# pqm_v2_page3.net
KiCad netlist of a schematic drawn in Altium Designer
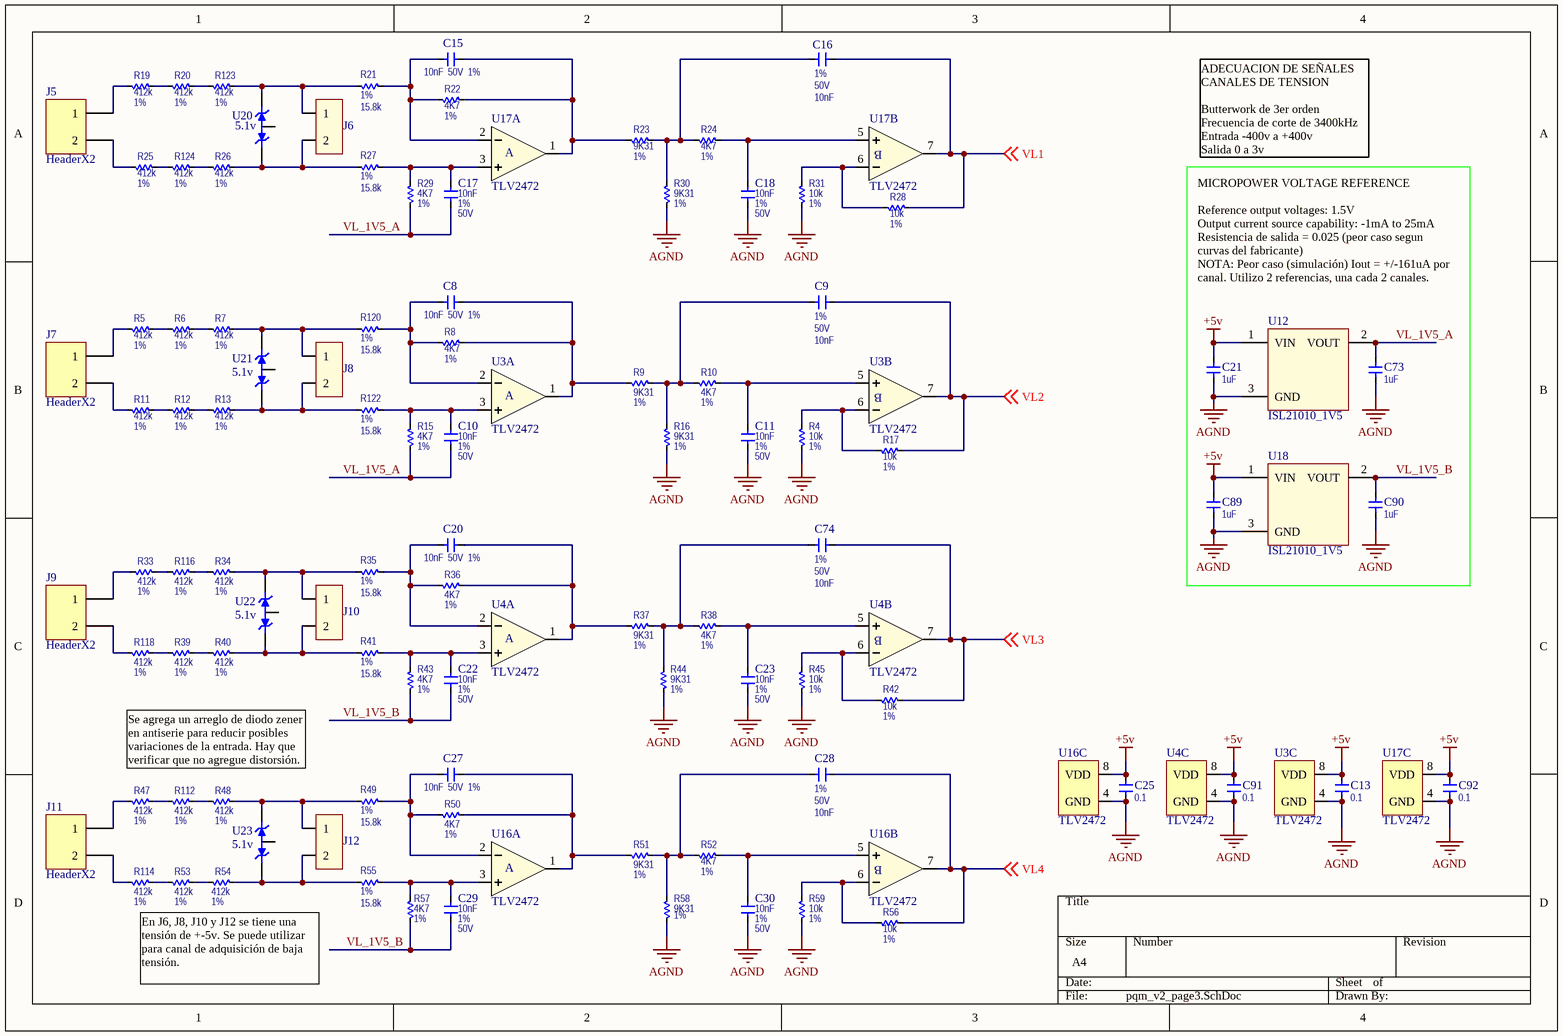
[diagram p0: pqm_v2_page3.SchDoc]

(export (version "E")
  (design (tool "Eeschema 10.0.6"))
  (components
    (comp (ref "C8")
      (value "10nF")
      (footprint "CAPC2013X110N")
      (description "CAP CER 10000PF 50V NP0 0805")
      (fields
        (field (name "MANUFACTURER") "Murata Electronics North America")
        (field (name "TOLERANCE") "1%")
        (field (name "VOLTAGE RATING") "50V")
        (field (name "DIGIKEY PART NUMBER") "490-8295-1-ND")
      )
      (libsource (lib "pqm_v2_lib_cap") (part "CAP_GRM2195C1H103FA01D_MURATA"))
    )
    (comp (ref "C9")
      (value "10nF")
      (footprint "CAPC2013X110N")
      (description "CAP CER 10000PF 50V NP0 0805")
      (fields
        (field (name "MANUFACTURER") "Murata Electronics North America")
        (field (name "TOLERANCE") "1%")
        (field (name "VOLTAGE RATING") "50V")
        (field (name "DIGIKEY PART NUMBER") "490-8295-1-ND")
      )
      (libsource (lib "pqm_v2_lib_cap") (part "CAP_GRM2195C1H103FA01D_MURATA"))
    )
    (comp (ref "C10")
      (value "10nF")
      (footprint "CAPC2013X110N")
      (description "CAP CER 10000PF 50V NP0 0805")
      (fields
        (field (name "MANUFACTURER") "Murata Electronics North America")
        (field (name "TOLERANCE") "1%")
        (field (name "VOLTAGE RATING") "50V")
        (field (name "DIGIKEY PART NUMBER") "490-8295-1-ND")
      )
      (libsource (lib "pqm_v2_lib_cap") (part "CAP_GRM2195C1H103FA01D_MURATA"))
    )
    (comp (ref "C11")
      (value "10nF")
      (footprint "CAPC2013X110N")
      (description "CAP CER 10000PF 50V NP0 0805")
      (fields
        (field (name "MANUFACTURER") "Murata Electronics North America")
        (field (name "TOLERANCE") "1%")
        (field (name "VOLTAGE RATING") "50V")
        (field (name "DIGIKEY PART NUMBER") "490-8295-1-ND")
      )
      (libsource (lib "pqm_v2_lib_cap") (part "CAP_GRM2195C1H103FA01D_MURATA"))
    )
    (comp (ref "C13")
      (value "0.1")
      (footprint "CAPC2013X110N")
      (description "CAP CER 0.1UF 25V 10% X7R 0805")
      (fields (field (name "MANUFACTURER") "Yageo") (field (name "TOLERANCE") "10%"))
      (libsource (lib "pqm_v2_lib_cap") (part "CAP_CC0805KRX7R8BB104_YAGEO"))
    )
    (comp (ref "C15")
      (value "10nF")
      (footprint "CAPC2013X110N")
      (description "CAP CER 10000PF 50V NP0 0805")
      (fields
        (field (name "MANUFACTURER") "Murata Electronics North America")
        (field (name "TOLERANCE") "1%")
        (field (name "VOLTAGE RATING") "50V")
        (field (name "DIGIKEY PART NUMBER") "490-8295-1-ND")
      )
      (libsource (lib "pqm_v2_lib_cap") (part "CAP_GRM2195C1H103FA01D_MURATA"))
    )
    (comp (ref "C16")
      (value "10nF")
      (footprint "CAPC2013X110N")
      (description "CAP CER 10000PF 50V NP0 0805")
      (fields
        (field (name "MANUFACTURER") "Murata Electronics North America")
        (field (name "TOLERANCE") "1%")
        (field (name "VOLTAGE RATING") "50V")
        (field (name "DIGIKEY PART NUMBER") "490-8295-1-ND")
      )
      (libsource (lib "pqm_v2_lib_cap") (part "CAP_GRM2195C1H103FA01D_MURATA"))
    )
    (comp (ref "C17")
      (value "10nF")
      (footprint "CAPC2013X110N")
      (description "CAP CER 10000PF 50V NP0 0805")
      (fields
        (field (name "MANUFACTURER") "Murata Electronics North America")
        (field (name "TOLERANCE") "1%")
        (field (name "VOLTAGE RATING") "50V")
        (field (name "DIGIKEY PART NUMBER") "490-8295-1-ND")
      )
      (libsource (lib "pqm_v2_lib_cap") (part "CAP_GRM2195C1H103FA01D_MURATA"))
    )
    (comp (ref "C18")
      (value "10nF")
      (footprint "CAPC2013X110N")
      (description "CAP CER 10000PF 50V NP0 0805")
      (fields
        (field (name "MANUFACTURER") "Murata Electronics North America")
        (field (name "TOLERANCE") "1%")
        (field (name "VOLTAGE RATING") "50V")
        (field (name "DIGIKEY PART NUMBER") "490-8295-1-ND")
      )
      (libsource (lib "pqm_v2_lib_cap") (part "CAP_GRM2195C1H103FA01D_MURATA"))
    )
    (comp (ref "C20")
      (value "10nF")
      (footprint "CAPC2013X110N")
      (description "CAP CER 10000PF 50V NP0 0805")
      (fields
        (field (name "MANUFACTURER") "Murata Electronics North America")
        (field (name "TOLERANCE") "1%")
        (field (name "VOLTAGE RATING") "50V")
        (field (name "DIGIKEY PART NUMBER") "490-8295-1-ND")
      )
      (libsource (lib "pqm_v2_lib_cap") (part "CAP_GRM2195C1H103FA01D_MURATA"))
    )
    (comp (ref "C21")
      (value "1uF")
      (footprint "CAPC2013X110N")
      (description "CAP CER 1UF 16V X7R 0805")
      (fields (field (name "MANUFACTURER") "YAGEO") (field (name "TOLERANCE") "10%"))
      (libsource (lib "pqm_v2_lib_cap") (part "CAP_CC0805KKX7R7BB105_YAGEO"))
    )
    (comp (ref "C22")
      (value "10nF")
      (footprint "CAPC2013X110N")
      (description "CAP CER 10000PF 50V NP0 0805")
      (fields
        (field (name "MANUFACTURER") "Murata Electronics North America")
        (field (name "TOLERANCE") "1%")
        (field (name "VOLTAGE RATING") "50V")
        (field (name "DIGIKEY PART NUMBER") "490-8295-1-ND")
      )
      (libsource (lib "pqm_v2_lib_cap") (part "CAP_GRM2195C1H103FA01D_MURATA"))
    )
    (comp (ref "C23")
      (value "10nF")
      (footprint "CAPC2013X110N")
      (description "CAP CER 10000PF 50V NP0 0805")
      (fields
        (field (name "MANUFACTURER") "Murata Electronics North America")
        (field (name "TOLERANCE") "1%")
        (field (name "VOLTAGE RATING") "50V")
        (field (name "DIGIKEY PART NUMBER") "490-8295-1-ND")
      )
      (libsource (lib "pqm_v2_lib_cap") (part "CAP_GRM2195C1H103FA01D_MURATA"))
    )
    (comp (ref "C25")
      (value "0.1")
      (footprint "CAPC2013X110N")
      (description "CAP CER 0.1UF 25V 10% X7R 0805")
      (fields (field (name "MANUFACTURER") "Yageo") (field (name "TOLERANCE") "10%"))
      (libsource (lib "pqm_v2_lib_cap") (part "CAP_CC0805KRX7R8BB104_YAGEO"))
    )
    (comp (ref "C27")
      (value "10nF")
      (footprint "CAPC2013X110N")
      (description "CAP CER 10000PF 50V NP0 0805")
      (fields
        (field (name "MANUFACTURER") "Murata Electronics North America")
        (field (name "TOLERANCE") "1%")
        (field (name "VOLTAGE RATING") "50V")
        (field (name "DIGIKEY PART NUMBER") "490-8295-1-ND")
      )
      (libsource (lib "pqm_v2_lib_cap") (part "CAP_GRM2195C1H103FA01D_MURATA"))
    )
    (comp (ref "C28")
      (value "10nF")
      (footprint "CAPC2013X110N")
      (description "CAP CER 10000PF 50V NP0 0805")
      (fields
        (field (name "MANUFACTURER") "Murata Electronics North America")
        (field (name "TOLERANCE") "1%")
        (field (name "VOLTAGE RATING") "50V")
        (field (name "DIGIKEY PART NUMBER") "490-8295-1-ND")
      )
      (libsource (lib "pqm_v2_lib_cap") (part "CAP_GRM2195C1H103FA01D_MURATA"))
    )
    (comp (ref "C29")
      (value "10nF")
      (footprint "CAPC2013X110N")
      (description "CAP CER 10000PF 50V NP0 0805")
      (fields
        (field (name "MANUFACTURER") "Murata Electronics North America")
        (field (name "TOLERANCE") "1%")
        (field (name "VOLTAGE RATING") "50V")
        (field (name "DIGIKEY PART NUMBER") "490-8295-1-ND")
      )
      (libsource (lib "pqm_v2_lib_cap") (part "CAP_GRM2195C1H103FA01D_MURATA"))
    )
    (comp (ref "C30")
      (value "10nF")
      (footprint "CAPC2013X110N")
      (description "CAP CER 10000PF 50V NP0 0805")
      (fields
        (field (name "MANUFACTURER") "Murata Electronics North America")
        (field (name "TOLERANCE") "1%")
        (field (name "VOLTAGE RATING") "50V")
        (field (name "DIGIKEY PART NUMBER") "490-8295-1-ND")
      )
      (libsource (lib "pqm_v2_lib_cap") (part "CAP_GRM2195C1H103FA01D_MURATA"))
    )
    (comp (ref "C73")
      (value "1uF")
      (footprint "CAPC2013X110N")
      (description "CAP CER 1UF 16V X7R 0805")
      (fields (field (name "MANUFACTURER") "YAGEO") (field (name "TOLERANCE") "10%"))
      (libsource (lib "pqm_v2_lib_cap") (part "CAP_CC0805KKX7R7BB105_YAGEO"))
    )
    (comp (ref "C74")
      (value "10nF")
      (footprint "CAPC2013X110N")
      (description "CAP CER 10000PF 50V NP0 0805")
      (fields
        (field (name "MANUFACTURER") "Murata Electronics North America")
        (field (name "TOLERANCE") "1%")
        (field (name "VOLTAGE RATING") "50V")
        (field (name "DIGIKEY PART NUMBER") "490-8295-1-ND")
      )
      (libsource (lib "pqm_v2_lib_cap") (part "CAP_GRM2195C1H103FA01D_MURATA"))
    )
    (comp (ref "C89")
      (value "1uF")
      (footprint "CAPC2013X110N")
      (description "CAP CER 1UF 16V X7R 0805")
      (fields (field (name "MANUFACTURER") "YAGEO") (field (name "TOLERANCE") "10%"))
      (libsource (lib "pqm_v2_lib_cap") (part "CAP_CC0805KKX7R7BB105_YAGEO"))
    )
    (comp (ref "C90")
      (value "1uF")
      (footprint "CAPC2013X110N")
      (description "CAP CER 1UF 16V X7R 0805")
      (fields (field (name "MANUFACTURER") "YAGEO") (field (name "TOLERANCE") "10%"))
      (libsource (lib "pqm_v2_lib_cap") (part "CAP_CC0805KKX7R7BB105_YAGEO"))
    )
    (comp (ref "C91")
      (value "0.1")
      (footprint "CAPC2013X110N")
      (description "CAP CER 0.1UF 25V 10% X7R 0805")
      (fields (field (name "MANUFACTURER") "Yageo") (field (name "TOLERANCE") "10%"))
      (libsource (lib "pqm_v2_lib_cap") (part "CAP_CC0805KRX7R8BB104_YAGEO"))
    )
    (comp (ref "C92")
      (value "0.1")
      (footprint "CAPC2013X110N")
      (description "CAP CER 0.1UF 25V 10% X7R 0805")
      (fields (field (name "MANUFACTURER") "Yageo") (field (name "TOLERANCE") "10%"))
      (libsource (lib "pqm_v2_lib_cap") (part "CAP_CC0805KRX7R8BB104_YAGEO"))
    )
    (comp (ref "J5")
      (value "HeaderX2")
      (footprint "PHOENIX_1729128")
      (libsource (lib "pqm_v2_lib_connectors") (part "CON_HeaderX2"))
    )
    (comp (ref "J6")
      (value "CON_RADX2")
      (footprint "RAD2")
      (libsource (lib "pqm_v2_lib_connectors") (part "CON_RADX2"))
    )
    (comp (ref "J7")
      (value "HeaderX2")
      (footprint "PHOENIX_1729128")
      (libsource (lib "pqm_v2_lib_connectors") (part "CON_HeaderX2"))
    )
    (comp (ref "J8")
      (value "CON_RADX2")
      (footprint "RAD2")
      (libsource (lib "pqm_v2_lib_connectors") (part "CON_RADX2"))
    )
    (comp (ref "J9")
      (value "HeaderX2")
      (footprint "PHOENIX_1729128")
      (libsource (lib "pqm_v2_lib_connectors") (part "CON_HeaderX2"))
    )
    (comp (ref "J10")
      (value "CON_RADX2")
      (footprint "RAD2")
      (libsource (lib "pqm_v2_lib_connectors") (part "CON_RADX2"))
    )
    (comp (ref "J11")
      (value "HeaderX2")
      (footprint "PHOENIX_1729128")
      (libsource (lib "pqm_v2_lib_connectors") (part "CON_HeaderX2"))
    )
    (comp (ref "J12")
      (value "CON_RADX2")
      (footprint "RAD2")
      (libsource (lib "pqm_v2_lib_connectors") (part "CON_RADX2"))
    )
    (comp (ref "R4")
      (value "10k")
      (footprint "RESC2013X065BN")
      (description "RES SMD 10K OHM 1% 1/8W 0805")
      (fields
        (field (name "TOLERANCE") "1%")
        (field (name "MANUFACTURER") "Yageo")
        (field (name "DIGIKEY PART NUMBER") "311-10.0KCRCT-ND")
      )
      (libsource (lib "pqm_v2_lib_res") (part "RES_RC0805FR-0710KL_YAGEO"))
    )
    (comp (ref "R5")
      (value "412k")
      (footprint "RESC2013X065BN")
      (description "RES SMD 412K OHM 1% 1/8W 0805")
      (fields
        (field (name "TOLERANCE") "1%")
        (field (name "MANUFACTURER") "Yageo")
        (field (name "DIGIKEY PART NUMBER") "311-412KCRCT-ND")
      )
      (libsource (lib "pqm_v2_lib_res") (part "RES_RC0805FR-07412KL_YAGEO"))
    )
    (comp (ref "R6")
      (value "412k")
      (footprint "RESC2013X065BN")
      (description "RES SMD 412K OHM 1% 1/8W 0805")
      (fields
        (field (name "TOLERANCE") "1%")
        (field (name "MANUFACTURER") "Yageo")
        (field (name "DIGIKEY PART NUMBER") "311-412KCRCT-ND")
      )
      (libsource (lib "pqm_v2_lib_res") (part "RES_RC0805FR-07412KL_YAGEO"))
    )
    (comp (ref "R7")
      (value "412k")
      (footprint "RESC2013X065BN")
      (description "RES SMD 412K OHM 1% 1/8W 0805")
      (fields
        (field (name "TOLERANCE") "1%")
        (field (name "MANUFACTURER") "Yageo")
        (field (name "DIGIKEY PART NUMBER") "311-412KCRCT-ND")
      )
      (libsource (lib "pqm_v2_lib_res") (part "RES_RC0805FR-07412KL_YAGEO"))
    )
    (comp (ref "R8")
      (value "4K7")
      (footprint "RESC2013X065BN")
      (description "RES SMD 4.7K OHM 1% 1/8W 0805")
      (fields
        (field (name "TOLERANCE") "1%")
        (field (name "MANUFACTURER") "Yageo")
        (field (name "DIGIKEY PART NUMBER") "311-4.70KCRCT-ND")
      )
      (libsource (lib "pqm_v2_lib_res") (part "RES_RC0805FR-074K7L_YAGEO"))
    )
    (comp (ref "R9")
      (value "9K31")
      (footprint "RESC2013X065BN")
      (description "RES SMD 9.31K OHM 1% 1/8W 0805")
      (fields
        (field (name "TOLERANCE") "1%")
        (field (name "MANUFACTURER") "Yageo")
        (field (name "DIGIKEY PART NUMBER") "311-9.31KCRCT-ND")
      )
      (libsource (lib "pqm_v2_lib_res") (part "RES_RC0805FR-079K31L_YAGEO"))
    )
    (comp (ref "R10")
      (value "4K7")
      (footprint "RESC2013X065BN")
      (description "RES SMD 4.7K OHM 1% 1/8W 0805")
      (fields
        (field (name "TOLERANCE") "1%")
        (field (name "MANUFACTURER") "Yageo")
        (field (name "DIGIKEY PART NUMBER") "311-4.70KCRCT-ND")
      )
      (libsource (lib "pqm_v2_lib_res") (part "RES_RC0805FR-074K7L_YAGEO"))
    )
    (comp (ref "R11")
      (value "412k")
      (footprint "RESC2013X065BN")
      (description "RES SMD 412K OHM 1% 1/8W 0805")
      (fields
        (field (name "TOLERANCE") "1%")
        (field (name "MANUFACTURER") "Yageo")
        (field (name "DIGIKEY PART NUMBER") "311-412KCRCT-ND")
      )
      (libsource (lib "pqm_v2_lib_res") (part "RES_RC0805FR-07412KL_YAGEO"))
    )
    (comp (ref "R12")
      (value "412k")
      (footprint "RESC2013X065BN")
      (description "RES SMD 412K OHM 1% 1/8W 0805")
      (fields
        (field (name "TOLERANCE") "1%")
        (field (name "MANUFACTURER") "Yageo")
        (field (name "DIGIKEY PART NUMBER") "311-412KCRCT-ND")
      )
      (libsource (lib "pqm_v2_lib_res") (part "RES_RC0805FR-07412KL_YAGEO"))
    )
    (comp (ref "R13")
      (value "412k")
      (footprint "RESC2013X065BN")
      (description "RES SMD 412K OHM 1% 1/8W 0805")
      (fields
        (field (name "TOLERANCE") "1%")
        (field (name "MANUFACTURER") "Yageo")
        (field (name "DIGIKEY PART NUMBER") "311-412KCRCT-ND")
      )
      (libsource (lib "pqm_v2_lib_res") (part "RES_RC0805FR-07412KL_YAGEO"))
    )
    (comp (ref "R15")
      (value "4K7")
      (footprint "RESC2013X065BN")
      (description "RES SMD 4.7K OHM 1% 1/8W 0805")
      (fields
        (field (name "TOLERANCE") "1%")
        (field (name "MANUFACTURER") "Yageo")
        (field (name "DIGIKEY PART NUMBER") "311-4.70KCRCT-ND")
      )
      (libsource (lib "pqm_v2_lib_res") (part "RES_RC0805FR-074K7L_YAGEO"))
    )
    (comp (ref "R16")
      (value "9K31")
      (footprint "RESC2013X065BN")
      (description "RES SMD 9.31K OHM 1% 1/8W 0805")
      (fields
        (field (name "TOLERANCE") "1%")
        (field (name "MANUFACTURER") "Yageo")
        (field (name "DIGIKEY PART NUMBER") "311-9.31KCRCT-ND")
      )
      (libsource (lib "pqm_v2_lib_res") (part "RES_RC0805FR-079K31L_YAGEO"))
    )
    (comp (ref "R17")
      (value "10k")
      (footprint "RESC2013X065BN")
      (description "RES SMD 10K OHM 1% 1/8W 0805")
      (fields
        (field (name "TOLERANCE") "1%")
        (field (name "MANUFACTURER") "Yageo")
        (field (name "DIGIKEY PART NUMBER") "311-10.0KCRCT-ND")
      )
      (libsource (lib "pqm_v2_lib_res") (part "RES_RC0805FR-0710KL_YAGEO"))
    )
    (comp (ref "R19")
      (value "412k")
      (footprint "RESC2013X065BN")
      (description "RES SMD 412K OHM 1% 1/8W 0805")
      (fields
        (field (name "TOLERANCE") "1%")
        (field (name "MANUFACTURER") "Yageo")
        (field (name "DIGIKEY PART NUMBER") "311-412KCRCT-ND")
      )
      (libsource (lib "pqm_v2_lib_res") (part "RES_RC0805FR-07412KL_YAGEO"))
    )
    (comp (ref "R20")
      (value "412k")
      (footprint "RESC2013X065BN")
      (description "RES SMD 412K OHM 1% 1/8W 0805")
      (fields
        (field (name "TOLERANCE") "1%")
        (field (name "MANUFACTURER") "Yageo")
        (field (name "DIGIKEY PART NUMBER") "311-412KCRCT-ND")
      )
      (libsource (lib "pqm_v2_lib_res") (part "RES_RC0805FR-07412KL_YAGEO"))
    )
    (comp (ref "R21")
      (value "15.8k")
      (footprint "RESC2013X065BN")
      (description "RES SMD 15.8K OHM 1% 1/8W 0805")
      (fields
        (field (name "MANUFACTURER") "Yageo")
        (field (name "DIGIKEY PART NUMBER") "311-15.8KCRCT-ND")
        (field (name "TOLERANCE") "1%")
      )
      (libsource (lib "pqm_v2_lib_res") (part "RES_RC0805FR-0715K8L_YAGEO"))
    )
    (comp (ref "R22")
      (value "4K7")
      (footprint "RESC2013X065BN")
      (description "RES SMD 4.7K OHM 1% 1/8W 0805")
      (fields
        (field (name "TOLERANCE") "1%")
        (field (name "MANUFACTURER") "Yageo")
        (field (name "DIGIKEY PART NUMBER") "311-4.70KCRCT-ND")
      )
      (libsource (lib "pqm_v2_lib_res") (part "RES_RC0805FR-074K7L_YAGEO"))
    )
    (comp (ref "R23")
      (value "9K31")
      (footprint "RESC2013X065BN")
      (description "RES SMD 9.31K OHM 1% 1/8W 0805")
      (fields
        (field (name "TOLERANCE") "1%")
        (field (name "MANUFACTURER") "Yageo")
        (field (name "DIGIKEY PART NUMBER") "311-9.31KCRCT-ND")
      )
      (libsource (lib "pqm_v2_lib_res") (part "RES_RC0805FR-079K31L_YAGEO"))
    )
    (comp (ref "R24")
      (value "4K7")
      (footprint "RESC2013X065BN")
      (description "RES SMD 4.7K OHM 1% 1/8W 0805")
      (fields
        (field (name "TOLERANCE") "1%")
        (field (name "MANUFACTURER") "Yageo")
        (field (name "DIGIKEY PART NUMBER") "311-4.70KCRCT-ND")
      )
      (libsource (lib "pqm_v2_lib_res") (part "RES_RC0805FR-074K7L_YAGEO"))
    )
    (comp (ref "R25")
      (value "412k")
      (footprint "RESC2013X065BN")
      (description "RES SMD 412K OHM 1% 1/8W 0805")
      (fields
        (field (name "TOLERANCE") "1%")
        (field (name "MANUFACTURER") "Yageo")
        (field (name "DIGIKEY PART NUMBER") "311-412KCRCT-ND")
      )
      (libsource (lib "pqm_v2_lib_res") (part "RES_RC0805FR-07412KL_YAGEO"))
    )
    (comp (ref "R26")
      (value "412k")
      (footprint "RESC2013X065BN")
      (description "RES SMD 412K OHM 1% 1/8W 0805")
      (fields
        (field (name "TOLERANCE") "1%")
        (field (name "MANUFACTURER") "Yageo")
        (field (name "DIGIKEY PART NUMBER") "311-412KCRCT-ND")
      )
      (libsource (lib "pqm_v2_lib_res") (part "RES_RC0805FR-07412KL_YAGEO"))
    )
    (comp (ref "R27")
      (value "15.8k")
      (footprint "RESC2013X065BN")
      (description "RES SMD 15.8K OHM 1% 1/8W 0805")
      (fields
        (field (name "MANUFACTURER") "Yageo")
        (field (name "DIGIKEY PART NUMBER") "311-15.8KCRCT-ND")
        (field (name "TOLERANCE") "1%")
      )
      (libsource (lib "pqm_v2_lib_res") (part "RES_RC0805FR-0715K8L_YAGEO"))
    )
    (comp (ref "R28")
      (value "10k")
      (footprint "RESC2013X065BN")
      (description "RES SMD 10K OHM 1% 1/8W 0805")
      (fields
        (field (name "TOLERANCE") "1%")
        (field (name "MANUFACTURER") "Yageo")
        (field (name "DIGIKEY PART NUMBER") "311-10.0KCRCT-ND")
      )
      (libsource (lib "pqm_v2_lib_res") (part "RES_RC0805FR-0710KL_YAGEO"))
    )
    (comp (ref "R29")
      (value "4K7")
      (footprint "RESC2013X065BN")
      (description "RES SMD 4.7K OHM 1% 1/8W 0805")
      (fields
        (field (name "TOLERANCE") "1%")
        (field (name "MANUFACTURER") "Yageo")
        (field (name "DIGIKEY PART NUMBER") "311-4.70KCRCT-ND")
      )
      (libsource (lib "pqm_v2_lib_res") (part "RES_RC0805FR-074K7L_YAGEO"))
    )
    (comp (ref "R30")
      (value "9K31")
      (footprint "RESC2013X065BN")
      (description "RES SMD 9.31K OHM 1% 1/8W 0805")
      (fields
        (field (name "TOLERANCE") "1%")
        (field (name "MANUFACTURER") "Yageo")
        (field (name "DIGIKEY PART NUMBER") "311-9.31KCRCT-ND")
      )
      (libsource (lib "pqm_v2_lib_res") (part "RES_RC0805FR-079K31L_YAGEO"))
    )
    (comp (ref "R31")
      (value "10k")
      (footprint "RESC2013X065BN")
      (description "RES SMD 10K OHM 1% 1/8W 0805")
      (fields
        (field (name "TOLERANCE") "1%")
        (field (name "MANUFACTURER") "Yageo")
        (field (name "DIGIKEY PART NUMBER") "311-10.0KCRCT-ND")
      )
      (libsource (lib "pqm_v2_lib_res") (part "RES_RC0805FR-0710KL_YAGEO"))
    )
    (comp (ref "R33")
      (value "412k")
      (footprint "RESC2013X065BN")
      (description "RES SMD 412K OHM 1% 1/8W 0805")
      (fields
        (field (name "TOLERANCE") "1%")
        (field (name "MANUFACTURER") "Yageo")
        (field (name "DIGIKEY PART NUMBER") "311-412KCRCT-ND")
      )
      (libsource (lib "pqm_v2_lib_res") (part "RES_RC0805FR-07412KL_YAGEO"))
    )
    (comp (ref "R34")
      (value "412k")
      (footprint "RESC2013X065BN")
      (description "RES SMD 412K OHM 1% 1/8W 0805")
      (fields
        (field (name "TOLERANCE") "1%")
        (field (name "MANUFACTURER") "Yageo")
        (field (name "DIGIKEY PART NUMBER") "311-412KCRCT-ND")
      )
      (libsource (lib "pqm_v2_lib_res") (part "RES_RC0805FR-07412KL_YAGEO"))
    )
    (comp (ref "R35")
      (value "15.8k")
      (footprint "RESC2013X065BN")
      (description "RES SMD 15.8K OHM 1% 1/8W 0805")
      (fields
        (field (name "MANUFACTURER") "Yageo")
        (field (name "DIGIKEY PART NUMBER") "311-15.8KCRCT-ND")
        (field (name "TOLERANCE") "1%")
      )
      (libsource (lib "pqm_v2_lib_res") (part "RES_RC0805FR-0715K8L_YAGEO"))
    )
    (comp (ref "R36")
      (value "4K7")
      (footprint "RESC2013X065BN")
      (description "RES SMD 4.7K OHM 1% 1/8W 0805")
      (fields
        (field (name "TOLERANCE") "1%")
        (field (name "MANUFACTURER") "Yageo")
        (field (name "DIGIKEY PART NUMBER") "311-4.70KCRCT-ND")
      )
      (libsource (lib "pqm_v2_lib_res") (part "RES_RC0805FR-074K7L_YAGEO"))
    )
    (comp (ref "R37")
      (value "9K31")
      (footprint "RESC2013X065BN")
      (description "RES SMD 9.31K OHM 1% 1/8W 0805")
      (fields
        (field (name "TOLERANCE") "1%")
        (field (name "MANUFACTURER") "Yageo")
        (field (name "DIGIKEY PART NUMBER") "311-9.31KCRCT-ND")
      )
      (libsource (lib "pqm_v2_lib_res") (part "RES_RC0805FR-079K31L_YAGEO"))
    )
    (comp (ref "R38")
      (value "4K7")
      (footprint "RESC2013X065BN")
      (description "RES SMD 4.7K OHM 1% 1/8W 0805")
      (fields
        (field (name "TOLERANCE") "1%")
        (field (name "MANUFACTURER") "Yageo")
        (field (name "DIGIKEY PART NUMBER") "311-4.70KCRCT-ND")
      )
      (libsource (lib "pqm_v2_lib_res") (part "RES_RC0805FR-074K7L_YAGEO"))
    )
    (comp (ref "R39")
      (value "412k")
      (footprint "RESC2013X065BN")
      (description "RES SMD 412K OHM 1% 1/8W 0805")
      (fields
        (field (name "TOLERANCE") "1%")
        (field (name "MANUFACTURER") "Yageo")
        (field (name "DIGIKEY PART NUMBER") "311-412KCRCT-ND")
      )
      (libsource (lib "pqm_v2_lib_res") (part "RES_RC0805FR-07412KL_YAGEO"))
    )
    (comp (ref "R40")
      (value "412k")
      (footprint "RESC2013X065BN")
      (description "RES SMD 412K OHM 1% 1/8W 0805")
      (fields
        (field (name "TOLERANCE") "1%")
        (field (name "MANUFACTURER") "Yageo")
        (field (name "DIGIKEY PART NUMBER") "311-412KCRCT-ND")
      )
      (libsource (lib "pqm_v2_lib_res") (part "RES_RC0805FR-07412KL_YAGEO"))
    )
    (comp (ref "R41")
      (value "15.8k")
      (footprint "RESC2013X065BN")
      (description "RES SMD 15.8K OHM 1% 1/8W 0805")
      (fields
        (field (name "MANUFACTURER") "Yageo")
        (field (name "DIGIKEY PART NUMBER") "311-15.8KCRCT-ND")
        (field (name "TOLERANCE") "1%")
      )
      (libsource (lib "pqm_v2_lib_res") (part "RES_RC0805FR-0715K8L_YAGEO"))
    )
    (comp (ref "R42")
      (value "10k")
      (footprint "RESC2013X065BN")
      (description "RES SMD 10K OHM 1% 1/8W 0805")
      (fields
        (field (name "TOLERANCE") "1%")
        (field (name "MANUFACTURER") "Yageo")
        (field (name "DIGIKEY PART NUMBER") "311-10.0KCRCT-ND")
      )
      (libsource (lib "pqm_v2_lib_res") (part "RES_RC0805FR-0710KL_YAGEO"))
    )
    (comp (ref "R43")
      (value "4K7")
      (footprint "RESC2013X065BN")
      (description "RES SMD 4.7K OHM 1% 1/8W 0805")
      (fields
        (field (name "TOLERANCE") "1%")
        (field (name "MANUFACTURER") "Yageo")
        (field (name "DIGIKEY PART NUMBER") "311-4.70KCRCT-ND")
      )
      (libsource (lib "pqm_v2_lib_res") (part "RES_RC0805FR-074K7L_YAGEO"))
    )
    (comp (ref "R44")
      (value "9K31")
      (footprint "RESC2013X065BN")
      (description "RES SMD 9.31K OHM 1% 1/8W 0805")
      (fields
        (field (name "TOLERANCE") "1%")
        (field (name "MANUFACTURER") "Yageo")
        (field (name "DIGIKEY PART NUMBER") "311-9.31KCRCT-ND")
      )
      (libsource (lib "pqm_v2_lib_res") (part "RES_RC0805FR-079K31L_YAGEO"))
    )
    (comp (ref "R45")
      (value "10k")
      (footprint "RESC2013X065BN")
      (description "RES SMD 10K OHM 1% 1/8W 0805")
      (fields
        (field (name "TOLERANCE") "1%")
        (field (name "MANUFACTURER") "Yageo")
        (field (name "DIGIKEY PART NUMBER") "311-10.0KCRCT-ND")
      )
      (libsource (lib "pqm_v2_lib_res") (part "RES_RC0805FR-0710KL_YAGEO"))
    )
    (comp (ref "R47")
      (value "412k")
      (footprint "RESC2013X065BN")
      (description "RES SMD 412K OHM 1% 1/8W 0805")
      (fields
        (field (name "TOLERANCE") "1%")
        (field (name "MANUFACTURER") "Yageo")
        (field (name "DIGIKEY PART NUMBER") "311-412KCRCT-ND")
      )
      (libsource (lib "pqm_v2_lib_res") (part "RES_RC0805FR-07412KL_YAGEO"))
    )
    (comp (ref "R48")
      (value "412k")
      (footprint "RESC2013X065BN")
      (description "RES SMD 412K OHM 1% 1/8W 0805")
      (fields
        (field (name "TOLERANCE") "1%")
        (field (name "MANUFACTURER") "Yageo")
        (field (name "DIGIKEY PART NUMBER") "311-412KCRCT-ND")
      )
      (libsource (lib "pqm_v2_lib_res") (part "RES_RC0805FR-07412KL_YAGEO"))
    )
    (comp (ref "R49")
      (value "15.8k")
      (footprint "RESC2013X065BN")
      (description "RES SMD 15.8K OHM 1% 1/8W 0805")
      (fields
        (field (name "MANUFACTURER") "Yageo")
        (field (name "DIGIKEY PART NUMBER") "311-15.8KCRCT-ND")
        (field (name "TOLERANCE") "1%")
      )
      (libsource (lib "pqm_v2_lib_res") (part "RES_RC0805FR-0715K8L_YAGEO"))
    )
    (comp (ref "R50")
      (value "4K7")
      (footprint "RESC2013X065BN")
      (description "RES SMD 4.7K OHM 1% 1/8W 0805")
      (fields
        (field (name "TOLERANCE") "1%")
        (field (name "MANUFACTURER") "Yageo")
        (field (name "DIGIKEY PART NUMBER") "311-4.70KCRCT-ND")
      )
      (libsource (lib "pqm_v2_lib_res") (part "RES_RC0805FR-074K7L_YAGEO"))
    )
    (comp (ref "R51")
      (value "9K31")
      (footprint "RESC2013X065BN")
      (description "RES SMD 9.31K OHM 1% 1/8W 0805")
      (fields
        (field (name "TOLERANCE") "1%")
        (field (name "MANUFACTURER") "Yageo")
        (field (name "DIGIKEY PART NUMBER") "311-9.31KCRCT-ND")
      )
      (libsource (lib "pqm_v2_lib_res") (part "RES_RC0805FR-079K31L_YAGEO"))
    )
    (comp (ref "R52")
      (value "4K7")
      (footprint "RESC2013X065BN")
      (description "RES SMD 4.7K OHM 1% 1/8W 0805")
      (fields
        (field (name "TOLERANCE") "1%")
        (field (name "MANUFACTURER") "Yageo")
        (field (name "DIGIKEY PART NUMBER") "311-4.70KCRCT-ND")
      )
      (libsource (lib "pqm_v2_lib_res") (part "RES_RC0805FR-074K7L_YAGEO"))
    )
    (comp (ref "R53")
      (value "412k")
      (footprint "RESC2013X065BN")
      (description "RES SMD 412K OHM 1% 1/8W 0805")
      (fields
        (field (name "TOLERANCE") "1%")
        (field (name "MANUFACTURER") "Yageo")
        (field (name "DIGIKEY PART NUMBER") "311-412KCRCT-ND")
      )
      (libsource (lib "pqm_v2_lib_res") (part "RES_RC0805FR-07412KL_YAGEO"))
    )
    (comp (ref "R54")
      (value "412k")
      (footprint "RESC2013X065BN")
      (description "RES SMD 412K OHM 1% 1/8W 0805")
      (fields
        (field (name "TOLERANCE") "1%")
        (field (name "MANUFACTURER") "Yageo")
        (field (name "DIGIKEY PART NUMBER") "311-412KCRCT-ND")
      )
      (libsource (lib "pqm_v2_lib_res") (part "RES_RC0805FR-07412KL_YAGEO"))
    )
    (comp (ref "R55")
      (value "15.8k")
      (footprint "RESC2013X065BN")
      (description "RES SMD 15.8K OHM 1% 1/8W 0805")
      (fields
        (field (name "MANUFACTURER") "Yageo")
        (field (name "DIGIKEY PART NUMBER") "311-15.8KCRCT-ND")
        (field (name "TOLERANCE") "1%")
      )
      (libsource (lib "pqm_v2_lib_res") (part "RES_RC0805FR-0715K8L_YAGEO"))
    )
    (comp (ref "R56")
      (value "10k")
      (footprint "RESC2013X065BN")
      (description "RES SMD 10K OHM 1% 1/8W 0805")
      (fields
        (field (name "TOLERANCE") "1%")
        (field (name "MANUFACTURER") "Yageo")
        (field (name "DIGIKEY PART NUMBER") "311-10.0KCRCT-ND")
      )
      (libsource (lib "pqm_v2_lib_res") (part "RES_RC0805FR-0710KL_YAGEO"))
    )
    (comp (ref "R57")
      (value "4K7")
      (footprint "RESC2013X065BN")
      (description "RES SMD 4.7K OHM 1% 1/8W 0805")
      (fields
        (field (name "TOLERANCE") "1%")
        (field (name "MANUFACTURER") "Yageo")
        (field (name "DIGIKEY PART NUMBER") "311-4.70KCRCT-ND")
      )
      (libsource (lib "pqm_v2_lib_res") (part "RES_RC0805FR-074K7L_YAGEO"))
    )
    (comp (ref "R58")
      (value "9K31")
      (footprint "RESC2013X065BN")
      (description "RES SMD 9.31K OHM 1% 1/8W 0805")
      (fields
        (field (name "TOLERANCE") "1%")
        (field (name "MANUFACTURER") "Yageo")
        (field (name "DIGIKEY PART NUMBER") "311-9.31KCRCT-ND")
      )
      (libsource (lib "pqm_v2_lib_res") (part "RES_RC0805FR-079K31L_YAGEO"))
    )
    (comp (ref "R59")
      (value "10k")
      (footprint "RESC2013X065BN")
      (description "RES SMD 10K OHM 1% 1/8W 0805")
      (fields
        (field (name "TOLERANCE") "1%")
        (field (name "MANUFACTURER") "Yageo")
        (field (name "DIGIKEY PART NUMBER") "311-10.0KCRCT-ND")
      )
      (libsource (lib "pqm_v2_lib_res") (part "RES_RC0805FR-0710KL_YAGEO"))
    )
    (comp (ref "R112")
      (value "412k")
      (footprint "RESC2013X065BN")
      (description "RES SMD 412K OHM 1% 1/8W 0805")
      (fields
        (field (name "TOLERANCE") "1%")
        (field (name "MANUFACTURER") "Yageo")
        (field (name "DIGIKEY PART NUMBER") "311-412KCRCT-ND")
      )
      (libsource (lib "pqm_v2_lib_res") (part "RES_RC0805FR-07412KL_YAGEO"))
    )
    (comp (ref "R114")
      (value "412k")
      (footprint "RESC2013X065BN")
      (description "RES SMD 412K OHM 1% 1/8W 0805")
      (fields
        (field (name "TOLERANCE") "1%")
        (field (name "MANUFACTURER") "Yageo")
        (field (name "DIGIKEY PART NUMBER") "311-412KCRCT-ND")
      )
      (libsource (lib "pqm_v2_lib_res") (part "RES_RC0805FR-07412KL_YAGEO"))
    )
    (comp (ref "R116")
      (value "412k")
      (footprint "RESC2013X065BN")
      (description "RES SMD 412K OHM 1% 1/8W 0805")
      (fields
        (field (name "TOLERANCE") "1%")
        (field (name "MANUFACTURER") "Yageo")
        (field (name "DIGIKEY PART NUMBER") "311-412KCRCT-ND")
      )
      (libsource (lib "pqm_v2_lib_res") (part "RES_RC0805FR-07412KL_YAGEO"))
    )
    (comp (ref "R118")
      (value "412k")
      (footprint "RESC2013X065BN")
      (description "RES SMD 412K OHM 1% 1/8W 0805")
      (fields
        (field (name "TOLERANCE") "1%")
        (field (name "MANUFACTURER") "Yageo")
        (field (name "DIGIKEY PART NUMBER") "311-412KCRCT-ND")
      )
      (libsource (lib "pqm_v2_lib_res") (part "RES_RC0805FR-07412KL_YAGEO"))
    )
    (comp (ref "R120")
      (value "15.8k")
      (footprint "RESC2013X065BN")
      (description "RES SMD 15.8K OHM 1% 1/8W 0805")
      (fields
        (field (name "MANUFACTURER") "Yageo")
        (field (name "DIGIKEY PART NUMBER") "311-15.8KCRCT-ND")
        (field (name "TOLERANCE") "1%")
      )
      (libsource (lib "pqm_v2_lib_res") (part "RES_RC0805FR-0715K8L_YAGEO"))
    )
    (comp (ref "R122")
      (value "15.8k")
      (footprint "RESC2013X065BN")
      (description "RES SMD 15.8K OHM 1% 1/8W 0805")
      (fields
        (field (name "MANUFACTURER") "Yageo")
        (field (name "DIGIKEY PART NUMBER") "311-15.8KCRCT-ND")
        (field (name "TOLERANCE") "1%")
      )
      (libsource (lib "pqm_v2_lib_res") (part "RES_RC0805FR-0715K8L_YAGEO"))
    )
    (comp (ref "R123")
      (value "412k")
      (footprint "RESC2013X065BN")
      (description "RES SMD 412K OHM 1% 1/8W 0805")
      (fields
        (field (name "TOLERANCE") "1%")
        (field (name "MANUFACTURER") "Yageo")
        (field (name "DIGIKEY PART NUMBER") "311-412KCRCT-ND")
      )
      (libsource (lib "pqm_v2_lib_res") (part "RES_RC0805FR-07412KL_YAGEO"))
    )
    (comp (ref "R124")
      (value "412k")
      (footprint "RESC2013X065BN")
      (description "RES SMD 412K OHM 1% 1/8W 0805")
      (fields
        (field (name "TOLERANCE") "1%")
        (field (name "MANUFACTURER") "Yageo")
        (field (name "DIGIKEY PART NUMBER") "311-412KCRCT-ND")
      )
      (libsource (lib "pqm_v2_lib_res") (part "RES_RC0805FR-07412KL_YAGEO"))
    )
    (comp (ref "U3")
      (value "TLV2472")
      (footprint "SOIC127P600-8BN")
      (description "IC OPAMP GP 2.8MHZ RRO 8SOIC")
      (fields
        (field (name "MANUFACTURER") "Texas Instrument")
        (field (name "DIGIKEY PART NUMBER") "296-2440-1-ND")
      )
      (libsource (lib "") (part "IC_TLV2472_ANALOG_1"))
    )
    (comp (ref "U4")
      (value "TLV2472")
      (footprint "SOIC127P600-8BN")
      (description "IC OPAMP GP 2.8MHZ RRO 8SOIC")
      (fields
        (field (name "MANUFACTURER") "Texas Instrument")
        (field (name "DIGIKEY PART NUMBER") "296-2440-1-ND")
      )
      (libsource (lib "pqm_v2_lib_ic") (part "IC_TLV2472_ANALOG"))
    )
    (comp (ref "U12")
      (value "ISL21010_1V5")
      (footprint "SOT23-3M")
      (description "IC VREF SERIES 1.5V SOT23-3")
      (fields
        (field (name "DIGIKEY PART NUMBER") "ISL21010CFH315Z-TKCT-ND")
        (field (name "MOUSER PART NUMBER") "968-ISL21010CFH315ZT")
      )
      (libsource (lib "pqm_v2_lib_ic") (part "IC_ISL21010_1V5_INTERSIL"))
    )
    (comp (ref "U16")
      (value "TLV2472")
      (footprint "SOIC127P600-8BN")
      (description "IC OPAMP GP 2.8MHZ RRO 8SOIC")
      (fields
        (field (name "MANUFACTURER") "Texas Instrument")
        (field (name "DIGIKEY PART NUMBER") "296-2440-1-ND")
      )
      (libsource (lib "") (part "IC_TLV2472_ANALOG_1"))
    )
    (comp (ref "U17")
      (value "TLV2472")
      (footprint "SOIC127P600-8BN")
      (description "IC OPAMP GP 2.8MHZ RRO 8SOIC")
      (fields
        (field (name "MANUFACTURER") "Texas Instrument")
        (field (name "DIGIKEY PART NUMBER") "296-2440-1-ND")
      )
      (libsource (lib "") (part "IC_TLV2472_ANALOG_1"))
    )
    (comp (ref "U18")
      (value "ISL21010_1V5")
      (footprint "SOT23-3M")
      (description "IC VREF SERIES 1.5V SOT23-3")
      (fields
        (field (name "DIGIKEY PART NUMBER") "ISL21010CFH315Z-TKCT-ND")
        (field (name "MOUSER PART NUMBER") "968-ISL21010CFH315ZT")
      )
      (libsource (lib "pqm_v2_lib_ic") (part "IC_ISL21010_1V5_INTERSIL"))
    )
    (comp (ref "U20")
      (value "IC_IAZ23C5V6-E3-18_VISHAY")
      (footprint "SOT23-3M")
      (description "DIODE ZENER ARRAY 5.6V SOT23")
      (fields
        (field (name "DIGIKEY PART NUMBER") "AZ23C5V6-E3-18CT-ND")
        (field (name "MANUFACTURER PART NUMBER") "AZ23C5V6-E3-18")
        (field (name "VOLTAGE") "5.1v")
      )
      (libsource (lib "pqm_v2_lib_ic") (part "IC_IAZ23C5V6-E3-18_VISHAY"))
    )
    (comp (ref "U21")
      (value "IC_IAZ23C5V6-E3-18_VISHAY")
      (footprint "SOT23-3M")
      (description "DIODE ZENER ARRAY 5.6V SOT23")
      (fields
        (field (name "DIGIKEY PART NUMBER") "AZ23C5V6-E3-18CT-ND")
        (field (name "MANUFACTURER PART NUMBER") "AZ23C5V6-E3-18")
        (field (name "VOLTAGE") "5.1v")
      )
      (libsource (lib "pqm_v2_lib_ic") (part "IC_IAZ23C5V6-E3-18_VISHAY"))
    )
    (comp (ref "U22")
      (value "IC_IAZ23C5V6-E3-18_VISHAY")
      (footprint "SOT23-3M")
      (description "DIODE ZENER ARRAY 5.6V SOT23")
      (fields
        (field (name "DIGIKEY PART NUMBER") "AZ23C5V6-E3-18CT-ND")
        (field (name "MANUFACTURER PART NUMBER") "AZ23C5V6-E3-18")
        (field (name "VOLTAGE") "5.1v")
      )
      (libsource (lib "pqm_v2_lib_ic") (part "IC_IAZ23C5V6-E3-18_VISHAY"))
    )
    (comp (ref "U23")
      (value "IC_IAZ23C5V6-E3-18_VISHAY")
      (footprint "SOT23-3M")
      (description "DIODE ZENER ARRAY 5.6V SOT23")
      (fields
        (field (name "DIGIKEY PART NUMBER") "AZ23C5V6-E3-18CT-ND")
        (field (name "MANUFACTURER PART NUMBER") "AZ23C5V6-E3-18")
        (field (name "VOLTAGE") "5.1v")
      )
      (libsource (lib "pqm_v2_lib_ic") (part "IC_IAZ23C5V6-E3-18_VISHAY"))
    )
  )
  (nets
    (net (code "1") (name "+5v") (class "Default")
      (node (ref "C13") (pin "1") (pinfunction "T1_1") (pintype "passive"))
      (node (ref "C21") (pin "1") (pinfunction "T1_1") (pintype "passive"))
      (node (ref "C25") (pin "1") (pinfunction "T1_1") (pintype "passive"))
      (node (ref "C89") (pin "1") (pinfunction "T1_1") (pintype "passive"))
      (node (ref "C91") (pin "1") (pinfunction "T1_1") (pintype "passive"))
      (node (ref "C92") (pin "1") (pinfunction "T1_1") (pintype "passive"))
      (node (ref "U12") (pin "1") (pinfunction "VIN_1") (pintype "passive"))
      (node (ref "U16") (pin "8") (pinfunction "VDD_8") (pintype "passive"))
      (node (ref "U17") (pin "8") (pinfunction "VDD_8") (pintype "passive"))
      (node (ref "U18") (pin "1") (pinfunction "VIN_1") (pintype "passive"))
      (node (ref "U3") (pin "8") (pinfunction "VDD_8") (pintype "passive"))
      (node (ref "U4") (pin "8") (pinfunction "VDD_8") (pintype "passive"))
    )
    (net (code "2") (name "/VL_1V5_A") (class "Default")
      (node (ref "C10") (pin "1") (pinfunction "T1_1") (pintype "passive"))
      (node (ref "C17") (pin "1") (pinfunction "T1_1") (pintype "passive"))
      (node (ref "C73") (pin "1") (pinfunction "T1_1") (pintype "passive"))
      (node (ref "R15") (pin "2") (pinfunction "T2_2") (pintype "passive"))
      (node (ref "R29") (pin "2") (pinfunction "T2_2") (pintype "passive"))
      (node (ref "U12") (pin "2") (pinfunction "VOUT_2") (pintype "passive"))
    )
    (net (code "3") (name "/VL_1V5_B") (class "Default")
      (node (ref "C22") (pin "1") (pinfunction "T1_1") (pintype "passive"))
      (node (ref "C29") (pin "1") (pinfunction "T1_1") (pintype "passive"))
      (node (ref "C90") (pin "1") (pinfunction "T1_1") (pintype "passive"))
      (node (ref "R43") (pin "2") (pinfunction "T2_2") (pintype "passive"))
      (node (ref "R57") (pin "2") (pinfunction "T2_2") (pintype "passive"))
      (node (ref "U18") (pin "2") (pinfunction "VOUT_2") (pintype "passive"))
    )
    (net (code "4") (name "AGND") (class "Default")
      (node (ref "C11") (pin "1") (pinfunction "T1_1") (pintype "passive"))
      (node (ref "C13") (pin "2") (pinfunction "T2_2") (pintype "passive"))
      (node (ref "C18") (pin "1") (pinfunction "T1_1") (pintype "passive"))
      (node (ref "C21") (pin "2") (pinfunction "T2_2") (pintype "passive"))
      (node (ref "C23") (pin "1") (pinfunction "T1_1") (pintype "passive"))
      (node (ref "C25") (pin "2") (pinfunction "T2_2") (pintype "passive"))
      (node (ref "C30") (pin "1") (pinfunction "T1_1") (pintype "passive"))
      (node (ref "C73") (pin "2") (pinfunction "T2_2") (pintype "passive"))
      (node (ref "C89") (pin "2") (pinfunction "T2_2") (pintype "passive"))
      (node (ref "C90") (pin "2") (pinfunction "T2_2") (pintype "passive"))
      (node (ref "C91") (pin "2") (pinfunction "T2_2") (pintype "passive"))
      (node (ref "C92") (pin "2") (pinfunction "T2_2") (pintype "passive"))
      (node (ref "R16") (pin "1") (pinfunction "T1_1") (pintype "passive"))
      (node (ref "R30") (pin "2") (pinfunction "T2_2") (pintype "passive"))
      (node (ref "R31") (pin "2") (pinfunction "T2_2") (pintype "passive"))
      (node (ref "R4") (pin "2") (pinfunction "T2_2") (pintype "passive"))
      (node (ref "R44") (pin "2") (pinfunction "T2_2") (pintype "passive"))
      (node (ref "R45") (pin "2") (pinfunction "T2_2") (pintype "passive"))
      (node (ref "R58") (pin "1") (pinfunction "T1_1") (pintype "passive"))
      (node (ref "R59") (pin "2") (pinfunction "T2_2") (pintype "passive"))
      (node (ref "U12") (pin "3") (pinfunction "GND_3") (pintype "passive"))
      (node (ref "U16") (pin "4") (pinfunction "GND_4") (pintype "passive"))
      (node (ref "U17") (pin "4") (pinfunction "GND_4") (pintype "passive"))
      (node (ref "U18") (pin "3") (pinfunction "GND_3") (pintype "passive"))
      (node (ref "U3") (pin "4") (pinfunction "GND_4") (pintype "passive"))
      (node (ref "U4") (pin "4") (pinfunction "GND_4") (pintype "passive"))
    )
    (net (code "5") (name "Net-(C8-T1)") (class "Default")
      (node (ref "C8") (pin "1") (pinfunction "T1_1") (pintype "passive"))
      (node (ref "R120") (pin "1") (pinfunction "T1_1") (pintype "passive"))
      (node (ref "R8") (pin "2") (pinfunction "T2_2") (pintype "passive"))
      (node (ref "U3") (pin "2") (pinfunction "INA-_2") (pintype "passive"))
    )
    (net (code "6") (name "Net-(C8-T2)") (class "Default")
      (node (ref "C8") (pin "2") (pinfunction "T2_2") (pintype "passive"))
      (node (ref "R8") (pin "1") (pinfunction "T1_1") (pintype "passive"))
      (node (ref "R9") (pin "2") (pinfunction "T2_2") (pintype "passive"))
      (node (ref "U3") (pin "1") (pinfunction "OUTA_1") (pintype "passive"))
    )
    (net (code "7") (name "Net-(C9-T1)") (class "Default")
      (node (ref "C9") (pin "1") (pinfunction "T1_1") (pintype "passive"))
      (node (ref "R10") (pin "2") (pinfunction "T2_2") (pintype "passive"))
      (node (ref "R16") (pin "2") (pinfunction "T2_2") (pintype "passive"))
      (node (ref "R9") (pin "1") (pinfunction "T1_1") (pintype "passive"))
    )
    (net (code "8") (name "Net-(C10-T2)") (class "Default")
      (node (ref "C10") (pin "2") (pinfunction "T2_2") (pintype "passive"))
      (node (ref "R122") (pin "1") (pinfunction "T1_1") (pintype "passive"))
      (node (ref "R15") (pin "1") (pinfunction "T1_1") (pintype "passive"))
      (node (ref "U3") (pin "3") (pinfunction "INA+_3") (pintype "passive"))
    )
    (net (code "9") (name "Net-(C11-T2)") (class "Default")
      (node (ref "C11") (pin "2") (pinfunction "T2_2") (pintype "passive"))
      (node (ref "R10") (pin "1") (pinfunction "T1_1") (pintype "passive"))
      (node (ref "U3") (pin "5") (pinfunction "INB+_5") (pintype "passive"))
    )
    (net (code "10") (name "Net-(C15-T1)") (class "Default")
      (node (ref "C15") (pin "1") (pinfunction "T1_1") (pintype "passive"))
      (node (ref "R21") (pin "1") (pinfunction "T1_1") (pintype "passive"))
      (node (ref "R22") (pin "2") (pinfunction "T2_2") (pintype "passive"))
      (node (ref "U17") (pin "2") (pinfunction "INA-_2") (pintype "passive"))
    )
    (net (code "11") (name "Net-(C15-T2)") (class "Default")
      (node (ref "C15") (pin "2") (pinfunction "T2_2") (pintype "passive"))
      (node (ref "R22") (pin "1") (pinfunction "T1_1") (pintype "passive"))
      (node (ref "R23") (pin "2") (pinfunction "T2_2") (pintype "passive"))
      (node (ref "U17") (pin "1") (pinfunction "OUTA_1") (pintype "passive"))
    )
    (net (code "12") (name "Net-(C16-T1)") (class "Default")
      (node (ref "C16") (pin "1") (pinfunction "T1_1") (pintype "passive"))
      (node (ref "R23") (pin "1") (pinfunction "T1_1") (pintype "passive"))
      (node (ref "R24") (pin "2") (pinfunction "T2_2") (pintype "passive"))
      (node (ref "R30") (pin "1") (pinfunction "T1_1") (pintype "passive"))
    )
    (net (code "13") (name "Net-(C17-T2)") (class "Default")
      (node (ref "C17") (pin "2") (pinfunction "T2_2") (pintype "passive"))
      (node (ref "R27") (pin "1") (pinfunction "T1_1") (pintype "passive"))
      (node (ref "R29") (pin "1") (pinfunction "T1_1") (pintype "passive"))
      (node (ref "U17") (pin "3") (pinfunction "INA+_3") (pintype "passive"))
    )
    (net (code "14") (name "Net-(C18-T2)") (class "Default")
      (node (ref "C18") (pin "2") (pinfunction "T2_2") (pintype "passive"))
      (node (ref "R24") (pin "1") (pinfunction "T1_1") (pintype "passive"))
      (node (ref "U17") (pin "5") (pinfunction "INB+_5") (pintype "passive"))
    )
    (net (code "15") (name "Net-(C20-T1)") (class "Default")
      (node (ref "C20") (pin "1") (pinfunction "T1_1") (pintype "passive"))
      (node (ref "R35") (pin "1") (pinfunction "T1_1") (pintype "passive"))
      (node (ref "R36") (pin "2") (pinfunction "T2_2") (pintype "passive"))
      (node (ref "U4") (pin "2") (pinfunction "INA-_2") (pintype "passive"))
    )
    (net (code "16") (name "Net-(C20-T2)") (class "Default")
      (node (ref "C20") (pin "2") (pinfunction "T2_2") (pintype "passive"))
      (node (ref "R36") (pin "1") (pinfunction "T1_1") (pintype "passive"))
      (node (ref "R37") (pin "2") (pinfunction "T2_2") (pintype "passive"))
      (node (ref "U4") (pin "1") (pinfunction "OUTA_1") (pintype "passive"))
    )
    (net (code "17") (name "Net-(C22-T2)") (class "Default")
      (node (ref "C22") (pin "2") (pinfunction "T2_2") (pintype "passive"))
      (node (ref "R41") (pin "1") (pinfunction "T1_1") (pintype "passive"))
      (node (ref "R43") (pin "1") (pinfunction "T1_1") (pintype "passive"))
      (node (ref "U4") (pin "3") (pinfunction "INA+_3") (pintype "passive"))
    )
    (net (code "18") (name "Net-(C23-T2)") (class "Default")
      (node (ref "C23") (pin "2") (pinfunction "T2_2") (pintype "passive"))
      (node (ref "R38") (pin "1") (pinfunction "T1_1") (pintype "passive"))
      (node (ref "U4") (pin "5") (pinfunction "INB+_5") (pintype "passive"))
    )
    (net (code "19") (name "Net-(C27-T1)") (class "Default")
      (node (ref "C27") (pin "1") (pinfunction "T1_1") (pintype "passive"))
      (node (ref "R49") (pin "1") (pinfunction "T1_1") (pintype "passive"))
      (node (ref "R50") (pin "2") (pinfunction "T2_2") (pintype "passive"))
      (node (ref "U16") (pin "2") (pinfunction "INA-_2") (pintype "passive"))
    )
    (net (code "20") (name "Net-(C27-T2)") (class "Default")
      (node (ref "C27") (pin "2") (pinfunction "T2_2") (pintype "passive"))
      (node (ref "R50") (pin "1") (pinfunction "T1_1") (pintype "passive"))
      (node (ref "R51") (pin "1") (pinfunction "T1_1") (pintype "passive"))
      (node (ref "U16") (pin "1") (pinfunction "OUTA_1") (pintype "passive"))
    )
    (net (code "21") (name "Net-(C28-T1)") (class "Default")
      (node (ref "C28") (pin "1") (pinfunction "T1_1") (pintype "passive"))
      (node (ref "R51") (pin "2") (pinfunction "T2_2") (pintype "passive"))
      (node (ref "R52") (pin "2") (pinfunction "T2_2") (pintype "passive"))
      (node (ref "R58") (pin "2") (pinfunction "T2_2") (pintype "passive"))
    )
    (net (code "22") (name "Net-(C29-T2)") (class "Default")
      (node (ref "C29") (pin "2") (pinfunction "T2_2") (pintype "passive"))
      (node (ref "R55") (pin "1") (pinfunction "T1_1") (pintype "passive"))
      (node (ref "R57") (pin "1") (pinfunction "T1_1") (pintype "passive"))
      (node (ref "U16") (pin "3") (pinfunction "INA+_3") (pintype "passive"))
    )
    (net (code "23") (name "Net-(C30-T2)") (class "Default")
      (node (ref "C30") (pin "2") (pinfunction "T2_2") (pintype "passive"))
      (node (ref "R52") (pin "1") (pinfunction "T1_1") (pintype "passive"))
      (node (ref "U16") (pin "5") (pinfunction "INB+_5") (pintype "passive"))
    )
    (net (code "24") (name "Net-(C74-T1)") (class "Default")
      (node (ref "C74") (pin "1") (pinfunction "T1_1") (pintype "passive"))
      (node (ref "R37") (pin "1") (pinfunction "T1_1") (pintype "passive"))
      (node (ref "R38") (pin "2") (pinfunction "T2_2") (pintype "passive"))
      (node (ref "R44") (pin "1") (pinfunction "T1_1") (pintype "passive"))
    )
    (net (code "25") (name "Net-(R5-T1)") (class "Default")
      (node (ref "R5") (pin "1") (pinfunction "T1_1") (pintype "passive"))
      (node (ref "R6") (pin "2") (pinfunction "T2_2") (pintype "passive"))
    )
    (net (code "26") (name "Net-(R5-T2)") (class "Default")
      (node (ref "J7") (pin "1") (pinfunction "1_1") (pintype "passive"))
      (node (ref "R5") (pin "2") (pinfunction "T2_2") (pintype "passive"))
    )
    (net (code "27") (name "Net-(R6-T1)") (class "Default")
      (node (ref "R6") (pin "1") (pinfunction "T1_1") (pintype "passive"))
      (node (ref "R7") (pin "2") (pinfunction "T2_2") (pintype "passive"))
    )
    (net (code "28") (name "Net-(R11-T1)") (class "Default")
      (node (ref "R11") (pin "1") (pinfunction "T1_1") (pintype "passive"))
      (node (ref "R12") (pin "2") (pinfunction "T2_2") (pintype "passive"))
    )
    (net (code "29") (name "Net-(R11-T2)") (class "Default")
      (node (ref "J7") (pin "2") (pinfunction "2_2") (pintype "passive"))
      (node (ref "R11") (pin "2") (pinfunction "T2_2") (pintype "passive"))
    )
    (net (code "30") (name "Net-(R12-T1)") (class "Default")
      (node (ref "R12") (pin "1") (pinfunction "T1_1") (pintype "passive"))
      (node (ref "R13") (pin "2") (pinfunction "T2_2") (pintype "passive"))
    )
    (net (code "31") (name "Net-(R17-T2)") (class "Default")
      (node (ref "R17") (pin "2") (pinfunction "T2_2") (pintype "passive"))
      (node (ref "R4") (pin "1") (pinfunction "T1_1") (pintype "passive"))
      (node (ref "U3") (pin "6") (pinfunction "INB-_6") (pintype "passive"))
    )
    (net (code "32") (name "Net-(R19-T1)") (class "Default")
      (node (ref "R19") (pin "1") (pinfunction "T1_1") (pintype "passive"))
      (node (ref "R20") (pin "2") (pinfunction "T2_2") (pintype "passive"))
    )
    (net (code "33") (name "Net-(R19-T2)") (class "Default")
      (node (ref "J5") (pin "1") (pinfunction "1_1") (pintype "passive"))
      (node (ref "R19") (pin "2") (pinfunction "T2_2") (pintype "passive"))
    )
    (net (code "34") (name "Net-(R25-T2)") (class "Default")
      (node (ref "J5") (pin "2") (pinfunction "2_2") (pintype "passive"))
      (node (ref "R25") (pin "2") (pinfunction "T2_2") (pintype "passive"))
    )
    (net (code "35") (name "Net-(R26-T1)") (class "Default")
      (node (ref "J6") (pin "2") (pinfunction "2_2") (pintype "passive"))
      (node (ref "R26") (pin "1") (pinfunction "T1_1") (pintype "passive"))
      (node (ref "R27") (pin "2") (pinfunction "T2_2") (pintype "passive"))
      (node (ref "U20") (pin "2") (pinfunction "2_2") (pintype "passive"))
    )
    (net (code "36") (name "Net-(R28-T2)") (class "Default")
      (node (ref "R28") (pin "2") (pinfunction "T2_2") (pintype "passive"))
      (node (ref "R31") (pin "1") (pinfunction "T1_1") (pintype "passive"))
      (node (ref "U17") (pin "6") (pinfunction "INB-_6") (pintype "passive"))
    )
    (net (code "37") (name "Net-(R33-T2)") (class "Default")
      (node (ref "J9") (pin "1") (pinfunction "1_1") (pintype "passive"))
      (node (ref "R33") (pin "2") (pinfunction "T2_2") (pintype "passive"))
    )
    (net (code "38") (name "Net-(R34-T1)") (class "Default")
      (node (ref "J10") (pin "1") (pinfunction "1_1") (pintype "passive"))
      (node (ref "R34") (pin "1") (pinfunction "T1_1") (pintype "passive"))
      (node (ref "R35") (pin "2") (pinfunction "T2_2") (pintype "passive"))
      (node (ref "U22") (pin "1") (pinfunction "1_1") (pintype "passive"))
    )
    (net (code "39") (name "Net-(R39-T1)") (class "Default")
      (node (ref "R39") (pin "1") (pinfunction "T1_1") (pintype "passive"))
      (node (ref "R40") (pin "2") (pinfunction "T2_2") (pintype "passive"))
    )
    (net (code "40") (name "Net-(R40-T1)") (class "Default")
      (node (ref "J10") (pin "2") (pinfunction "2_2") (pintype "passive"))
      (node (ref "R40") (pin "1") (pinfunction "T1_1") (pintype "passive"))
      (node (ref "R41") (pin "2") (pinfunction "T2_2") (pintype "passive"))
      (node (ref "U22") (pin "2") (pinfunction "2_2") (pintype "passive"))
    )
    (net (code "41") (name "Net-(R42-T2)") (class "Default")
      (node (ref "R42") (pin "2") (pinfunction "T2_2") (pintype "passive"))
      (node (ref "R45") (pin "1") (pinfunction "T1_1") (pintype "passive"))
      (node (ref "U4") (pin "6") (pinfunction "INB-_6") (pintype "passive"))
    )
    (net (code "42") (name "Net-(R47-T2)") (class "Default")
      (node (ref "J11") (pin "1") (pinfunction "1_1") (pintype "passive"))
      (node (ref "R47") (pin "2") (pinfunction "T2_2") (pintype "passive"))
    )
    (net (code "43") (name "Net-(R48-T1)") (class "Default")
      (node (ref "J12") (pin "1") (pinfunction "1_1") (pintype "passive"))
      (node (ref "R48") (pin "1") (pinfunction "T1_1") (pintype "passive"))
      (node (ref "R49") (pin "2") (pinfunction "T2_2") (pintype "passive"))
      (node (ref "U23") (pin "1") (pinfunction "1_1") (pintype "passive"))
    )
    (net (code "44") (name "Net-(R53-T1)") (class "Default")
      (node (ref "R53") (pin "1") (pinfunction "T1_1") (pintype "passive"))
      (node (ref "R54") (pin "2") (pinfunction "T2_2") (pintype "passive"))
    )
    (net (code "45") (name "Net-(R54-T1)") (class "Default")
      (node (ref "J12") (pin "2") (pinfunction "2_2") (pintype "passive"))
      (node (ref "R54") (pin "1") (pinfunction "T1_1") (pintype "passive"))
      (node (ref "R55") (pin "2") (pinfunction "T2_2") (pintype "passive"))
      (node (ref "U23") (pin "2") (pinfunction "2_2") (pintype "passive"))
    )
    (net (code "46") (name "Net-(R56-T2)") (class "Default")
      (node (ref "R56") (pin "2") (pinfunction "T2_2") (pintype "passive"))
      (node (ref "R59") (pin "1") (pinfunction "T1_1") (pintype "passive"))
      (node (ref "U16") (pin "6") (pinfunction "INB-_6") (pintype "passive"))
    )
    (net (code "47") (name "Net-(R112-T1)") (class "Default")
      (node (ref "R112") (pin "1") (pinfunction "T1_1") (pintype "passive"))
      (node (ref "R48") (pin "2") (pinfunction "T2_2") (pintype "passive"))
    )
    (net (code "48") (name "Net-(R112-T2)") (class "Default")
      (node (ref "R112") (pin "2") (pinfunction "T2_2") (pintype "passive"))
      (node (ref "R47") (pin "1") (pinfunction "T1_1") (pintype "passive"))
    )
    (net (code "49") (name "Net-(R114-T1)") (class "Default")
      (node (ref "R114") (pin "1") (pinfunction "T1_1") (pintype "passive"))
      (node (ref "R53") (pin "2") (pinfunction "T2_2") (pintype "passive"))
    )
    (net (code "50") (name "Net-(R114-T2)") (class "Default")
      (node (ref "J11") (pin "2") (pinfunction "2_2") (pintype "passive"))
      (node (ref "R114") (pin "2") (pinfunction "T2_2") (pintype "passive"))
    )
    (net (code "51") (name "Net-(R116-T1)") (class "Default")
      (node (ref "R116") (pin "1") (pinfunction "T1_1") (pintype "passive"))
      (node (ref "R34") (pin "2") (pinfunction "T2_2") (pintype "passive"))
    )
    (net (code "52") (name "Net-(R116-T2)") (class "Default")
      (node (ref "R116") (pin "2") (pinfunction "T2_2") (pintype "passive"))
      (node (ref "R33") (pin "1") (pinfunction "T1_1") (pintype "passive"))
    )
    (net (code "53") (name "Net-(R118-T1)") (class "Default")
      (node (ref "R118") (pin "1") (pinfunction "T1_1") (pintype "passive"))
      (node (ref "R39") (pin "2") (pinfunction "T2_2") (pintype "passive"))
    )
    (net (code "54") (name "Net-(R118-T2)") (class "Default")
      (node (ref "J9") (pin "2") (pinfunction "2_2") (pintype "passive"))
      (node (ref "R118") (pin "2") (pinfunction "T2_2") (pintype "passive"))
    )
    (net (code "55") (name "Net-(R120-T2)") (class "Default")
      (node (ref "J8") (pin "1") (pinfunction "1_1") (pintype "passive"))
      (node (ref "R120") (pin "2") (pinfunction "T2_2") (pintype "passive"))
      (node (ref "R7") (pin "1") (pinfunction "T1_1") (pintype "passive"))
      (node (ref "U21") (pin "1") (pinfunction "1_1") (pintype "passive"))
    )
    (net (code "56") (name "Net-(R122-T2)") (class "Default")
      (node (ref "J8") (pin "2") (pinfunction "2_2") (pintype "passive"))
      (node (ref "R122") (pin "2") (pinfunction "T2_2") (pintype "passive"))
      (node (ref "R13") (pin "1") (pinfunction "T1_1") (pintype "passive"))
      (node (ref "U21") (pin "2") (pinfunction "2_2") (pintype "passive"))
    )
    (net (code "57") (name "Net-(R123-T1)") (class "Default")
      (node (ref "J6") (pin "1") (pinfunction "1_1") (pintype "passive"))
      (node (ref "R123") (pin "1") (pinfunction "T1_1") (pintype "passive"))
      (node (ref "R21") (pin "2") (pinfunction "T2_2") (pintype "passive"))
      (node (ref "U20") (pin "1") (pinfunction "1_1") (pintype "passive"))
    )
    (net (code "58") (name "Net-(R123-T2)") (class "Default")
      (node (ref "R123") (pin "2") (pinfunction "T2_2") (pintype "passive"))
      (node (ref "R20") (pin "1") (pinfunction "T1_1") (pintype "passive"))
    )
    (net (code "59") (name "Net-(R124-T1)") (class "Default")
      (node (ref "R124") (pin "1") (pinfunction "T1_1") (pintype "passive"))
      (node (ref "R26") (pin "2") (pinfunction "T2_2") (pintype "passive"))
    )
    (net (code "60") (name "Net-(R124-T2)") (class "Default")
      (node (ref "R124") (pin "2") (pinfunction "T2_2") (pintype "passive"))
      (node (ref "R25") (pin "1") (pinfunction "T1_1") (pintype "passive"))
    )
    (net (code "61") (name "VL1") (class "Default")
      (node (ref "C16") (pin "2") (pinfunction "T2_2") (pintype "passive"))
      (node (ref "R28") (pin "1") (pinfunction "T1_1") (pintype "passive"))
      (node (ref "U17") (pin "7") (pinfunction "OUTB_7") (pintype "passive"))
    )
    (net (code "62") (name "VL2") (class "Default")
      (node (ref "C9") (pin "2") (pinfunction "T2_2") (pintype "passive"))
      (node (ref "R17") (pin "1") (pinfunction "T1_1") (pintype "passive"))
      (node (ref "U3") (pin "7") (pinfunction "OUTB_7") (pintype "passive"))
    )
    (net (code "63") (name "VL3") (class "Default")
      (node (ref "C74") (pin "2") (pinfunction "T2_2") (pintype "passive"))
      (node (ref "R42") (pin "1") (pinfunction "T1_1") (pintype "passive"))
      (node (ref "U4") (pin "7") (pinfunction "OUTB_7") (pintype "passive"))
    )
    (net (code "64") (name "VL4") (class "Default")
      (node (ref "C28") (pin "2") (pinfunction "T2_2") (pintype "passive"))
      (node (ref "R56") (pin "1") (pinfunction "T1_1") (pintype "passive"))
      (node (ref "U16") (pin "7") (pinfunction "OUTB_7") (pintype "passive"))
    )
    (net (code "65") (name "unconnected-(U20-Pad3)") (class "Default")
      (node (ref "U20") (pin "3") (pinfunction "3_3") (pintype "passive"))
    )
    (net (code "66") (name "unconnected-(U21-Pad3)") (class "Default")
      (node (ref "U21") (pin "3") (pinfunction "3_3") (pintype "passive"))
    )
    (net (code "67") (name "unconnected-(U22-Pad3)") (class "Default")
      (node (ref "U22") (pin "3") (pinfunction "3_3") (pintype "passive"))
    )
    (net (code "68") (name "unconnected-(U23-Pad3)") (class "Default")
      (node (ref "U23") (pin "3") (pinfunction "3_3") (pintype "passive"))
    )
  )
)
